# buttonpad.net
KiCad netlist of a schematic drawn in EAGLE
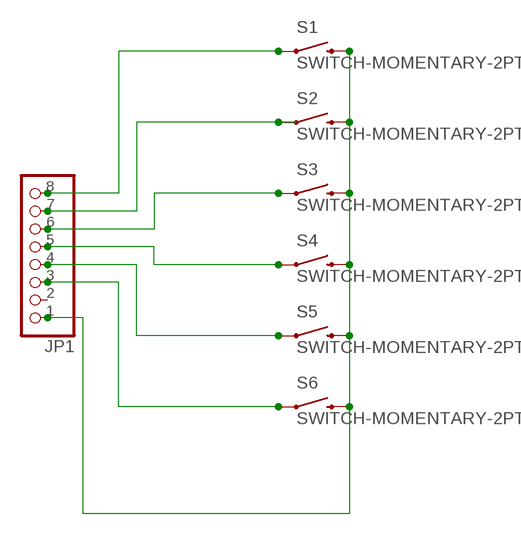
[diagram p0: schematic, sheet 1]

(export (version "E")
  (design (tool "Eeschema 10.0.6"))
  (components
    (comp (ref "JP1")
      (value "PINHD-1X8")
      (footprint "eagle-import:1X08")
      (libsource (lib "eagle-import") (part "PINHD-1X8"))
    )
    (comp (ref "S1")
      (value "SWITCH-MOMENTARY-2PTH")
      (footprint "eagle-import:TACTILE-PTH")
      (libsource (lib "eagle-import") (part "SWITCH-MOMENTARY-2PTH"))
    )
    (comp (ref "S2")
      (value "SWITCH-MOMENTARY-2PTH")
      (footprint "eagle-import:TACTILE-PTH")
      (libsource (lib "eagle-import") (part "SWITCH-MOMENTARY-2PTH"))
    )
    (comp (ref "S3")
      (value "SWITCH-MOMENTARY-2PTH")
      (footprint "eagle-import:TACTILE-PTH")
      (libsource (lib "eagle-import") (part "SWITCH-MOMENTARY-2PTH"))
    )
    (comp (ref "S4")
      (value "SWITCH-MOMENTARY-2PTH")
      (footprint "eagle-import:TACTILE-PTH")
      (libsource (lib "eagle-import") (part "SWITCH-MOMENTARY-2PTH"))
    )
    (comp (ref "S5")
      (value "SWITCH-MOMENTARY-2PTH")
      (footprint "eagle-import:TACTILE-PTH")
      (libsource (lib "eagle-import") (part "SWITCH-MOMENTARY-2PTH"))
    )
    (comp (ref "S6")
      (value "SWITCH-MOMENTARY-2PTH")
      (footprint "eagle-import:TACTILE-PTH")
      (libsource (lib "eagle-import") (part "SWITCH-MOMENTARY-2PTH"))
    )
  )
  (nets
    (net (code "1") (name "Net-(JP1-Pad3)") (class "Default")
      (node (ref "JP1") (pin "3") (pinfunction "3_3") (pintype "passive"))
      (node (ref "S6") (pin "1") (pinfunction "1_1") (pintype "passive"))
    )
    (net (code "2") (name "Net-(JP1-Pad4)") (class "Default")
      (node (ref "JP1") (pin "4") (pinfunction "4_4") (pintype "passive"))
      (node (ref "S5") (pin "1") (pinfunction "1_1") (pintype "passive"))
    )
    (net (code "3") (name "Net-(JP1-Pad5)") (class "Default")
      (node (ref "JP1") (pin "5") (pinfunction "5_5") (pintype "passive"))
      (node (ref "S4") (pin "1") (pinfunction "1_1") (pintype "passive"))
    )
    (net (code "4") (name "Net-(JP1-Pad6)") (class "Default")
      (node (ref "JP1") (pin "6") (pinfunction "6_6") (pintype "passive"))
      (node (ref "S3") (pin "1") (pinfunction "1_1") (pintype "passive"))
    )
    (net (code "5") (name "Net-(JP1-Pad7)") (class "Default")
      (node (ref "JP1") (pin "7") (pinfunction "7_7") (pintype "passive"))
      (node (ref "S2") (pin "1") (pinfunction "1_1") (pintype "passive"))
    )
    (net (code "6") (name "Net-(JP1-Pad8)") (class "Default")
      (node (ref "JP1") (pin "8") (pinfunction "8_8") (pintype "passive"))
      (node (ref "S1") (pin "1") (pinfunction "1_1") (pintype "passive"))
    )
    (net (code "7") (name "Net-(S1-2)") (class "Default")
      (node (ref "JP1") (pin "1") (pinfunction "1_1") (pintype "passive"))
      (node (ref "S1") (pin "3") (pinfunction "2_3") (pintype "passive"))
      (node (ref "S2") (pin "3") (pinfunction "2_3") (pintype "passive"))
      (node (ref "S3") (pin "3") (pinfunction "2_3") (pintype "passive"))
      (node (ref "S4") (pin "3") (pinfunction "2_3") (pintype "passive"))
      (node (ref "S5") (pin "3") (pinfunction "2_3") (pintype "passive"))
      (node (ref "S6") (pin "3") (pinfunction "2_3") (pintype "passive"))
    )
    (net (code "8") (name "unconnected-(JP1-Pad2)") (class "Default")
      (node (ref "JP1") (pin "2") (pinfunction "2_2") (pintype "passive"))
    )
  )
)
